# TRNG.net
KiCad netlist of a schematic drawn in EAGLE
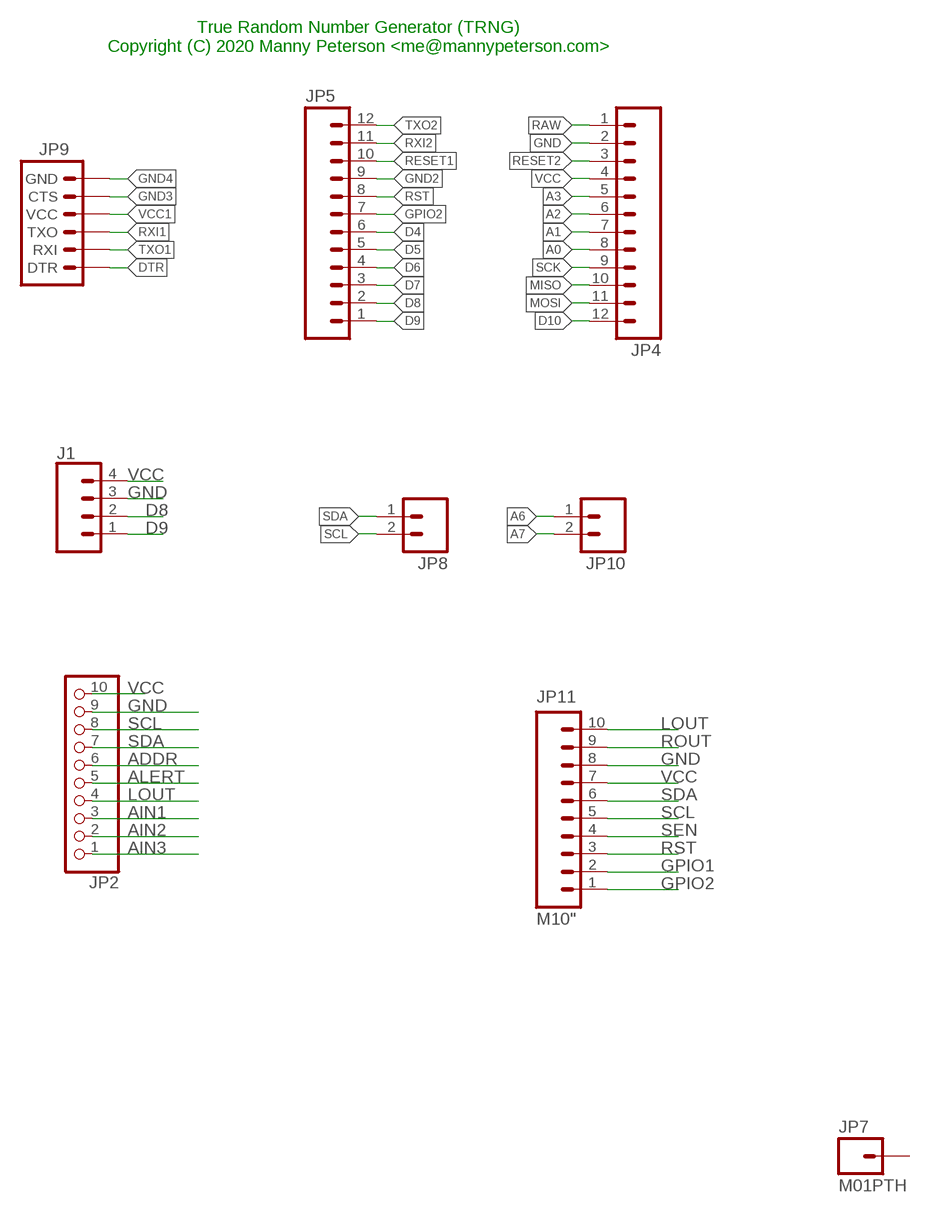
[diagram p0: schematic, sheet 1]

(export (version "E")
  (design (tool "Eeschema 10.0.6"))
  (components
    (comp (ref "J1")
      (value "CONN_04PTH")
      (footprint "eagle-import:1X04")
      (libsource (lib "eagle-import") (part "CONN_04PTH"))
    )
    (comp (ref "JP2")
      (value "HEADER-1X1070MIL")
      (footprint "eagle-import:1X10_ROUND70")
      (libsource (lib "eagle-import") (part "HEADER-1X1070MIL"))
    )
    (comp (ref "JP4")
      (value "M12PTH")
      (footprint "eagle-import:1X12")
      (libsource (lib "eagle-import") (part "M12PTH"))
    )
    (comp (ref "JP5")
      (value "M12PTH")
      (footprint "eagle-import:1X12")
      (libsource (lib "eagle-import") (part "M12PTH"))
    )
    (comp (ref "JP7")
      (value "M01PTH")
      (footprint "eagle-import:1X01")
      (libsource (lib "eagle-import") (part "M01PTH"))
    )
    (comp (ref "JP8")
      (value "M02PTH")
      (footprint "eagle-import:1X02")
      (libsource (lib "eagle-import") (part "M02PTH"))
    )
    (comp (ref "JP9")
      (value "ARDUINO_SERIAL_PROGRAMPTH")
      (footprint "eagle-import:1X06")
      (libsource (lib "eagle-import") (part "ARDUINO_SERIAL_PROGRAMPTH"))
    )
    (comp (ref "JP10")
      (value "M02PTH")
      (footprint "eagle-import:1X02")
      (libsource (lib "eagle-import") (part "M02PTH"))
    )
    (comp (ref "JP11")
      (value "M10\"")
      (footprint "eagle-import:1X10")
      (libsource (lib "eagle-import") (part "M10{dblquote}"))
    )
  )
  (nets
    (net (code "1") (name "/ADDR") (class "Default")
      (node (ref "JP2") (pin "6") (pinfunction "6_6") (pintype "passive"))
    )
    (net (code "2") (name "/AIN1") (class "Default")
      (node (ref "JP2") (pin "3") (pinfunction "3_3") (pintype "passive"))
    )
    (net (code "3") (name "/AIN2") (class "Default")
      (node (ref "JP2") (pin "2") (pinfunction "2_2") (pintype "passive"))
    )
    (net (code "4") (name "/AIN3") (class "Default")
      (node (ref "JP2") (pin "1") (pinfunction "1_1") (pintype "passive"))
    )
    (net (code "5") (name "/ALERT") (class "Default")
      (node (ref "JP2") (pin "5") (pinfunction "5_5") (pintype "passive"))
    )
    (net (code "6") (name "/GPIO1") (class "Default")
      (node (ref "JP11") (pin "2") (pinfunction "2_2") (pintype "passive"))
    )
    (net (code "7") (name "/LOUT") (class "Default")
      (node (ref "JP11") (pin "10") (pinfunction "10_10") (pintype "passive"))
      (node (ref "JP2") (pin "4") (pinfunction "4_4") (pintype "passive"))
    )
    (net (code "8") (name "/ROUT") (class "Default")
      (node (ref "JP11") (pin "9") (pinfunction "9_9") (pintype "passive"))
    )
    (net (code "9") (name "/SEN") (class "Default")
      (node (ref "JP11") (pin "4") (pinfunction "4_4") (pintype "passive"))
    )
    (net (code "10") (name "A0") (class "Default")
      (node (ref "JP4") (pin "8") (pinfunction "8_8") (pintype "passive"))
    )
    (net (code "11") (name "A1") (class "Default")
      (node (ref "JP4") (pin "7") (pinfunction "7_7") (pintype "passive"))
    )
    (net (code "12") (name "A2") (class "Default")
      (node (ref "JP4") (pin "6") (pinfunction "6_6") (pintype "passive"))
    )
    (net (code "13") (name "A3") (class "Default")
      (node (ref "JP4") (pin "5") (pinfunction "5_5") (pintype "passive"))
    )
    (net (code "14") (name "A6") (class "Default")
      (node (ref "JP10") (pin "1") (pinfunction "1_1") (pintype "passive"))
    )
    (net (code "15") (name "A7") (class "Default")
      (node (ref "JP10") (pin "2") (pinfunction "2_2") (pintype "passive"))
    )
    (net (code "16") (name "D4") (class "Default")
      (node (ref "JP5") (pin "6") (pinfunction "6_6") (pintype "passive"))
    )
    (net (code "17") (name "D5") (class "Default")
      (node (ref "JP5") (pin "5") (pinfunction "5_5") (pintype "passive"))
    )
    (net (code "18") (name "D6") (class "Default")
      (node (ref "JP5") (pin "4") (pinfunction "4_4") (pintype "passive"))
    )
    (net (code "19") (name "D7") (class "Default")
      (node (ref "JP5") (pin "3") (pinfunction "3_3") (pintype "passive"))
    )
    (net (code "20") (name "D8") (class "Default")
      (node (ref "J1") (pin "2") (pinfunction "2_2") (pintype "passive"))
      (node (ref "JP5") (pin "2") (pinfunction "2_2") (pintype "passive"))
    )
    (net (code "21") (name "D9") (class "Default")
      (node (ref "J1") (pin "1") (pinfunction "1_1") (pintype "passive"))
      (node (ref "JP5") (pin "1") (pinfunction "1_1") (pintype "passive"))
    )
    (net (code "22") (name "D10") (class "Default")
      (node (ref "JP4") (pin "12") (pinfunction "12_12") (pintype "passive"))
    )
    (net (code "23") (name "DTR") (class "Default")
      (node (ref "JP9") (pin "1") (pinfunction "DTR_1") (pintype "passive"))
    )
    (net (code "24") (name "GND") (class "Default")
      (node (ref "J1") (pin "3") (pinfunction "3_3") (pintype "passive"))
      (node (ref "JP11") (pin "8") (pinfunction "8_8") (pintype "passive"))
      (node (ref "JP2") (pin "9") (pinfunction "9_9") (pintype "passive"))
      (node (ref "JP4") (pin "2") (pinfunction "2_2") (pintype "passive"))
    )
    (net (code "25") (name "GND2") (class "Default")
      (node (ref "JP5") (pin "9") (pinfunction "9_9") (pintype "passive"))
    )
    (net (code "26") (name "GND3") (class "Default")
      (node (ref "JP9") (pin "5") (pinfunction "CTS_5") (pintype "passive"))
    )
    (net (code "27") (name "GND4") (class "Default")
      (node (ref "JP9") (pin "6") (pinfunction "GND_6") (pintype "passive"))
    )
    (net (code "28") (name "GPIO2") (class "Default")
      (node (ref "JP11") (pin "1") (pinfunction "1_1") (pintype "passive"))
      (node (ref "JP5") (pin "7") (pinfunction "7_7") (pintype "passive"))
    )
    (net (code "29") (name "MISO") (class "Default")
      (node (ref "JP4") (pin "10") (pinfunction "10_10") (pintype "passive"))
    )
    (net (code "30") (name "MOSI") (class "Default")
      (node (ref "JP4") (pin "11") (pinfunction "11_11") (pintype "passive"))
    )
    (net (code "31") (name "RAW") (class "Default")
      (node (ref "JP4") (pin "1") (pinfunction "1_1") (pintype "passive"))
    )
    (net (code "32") (name "RESET1") (class "Default")
      (node (ref "JP5") (pin "10") (pinfunction "10_10") (pintype "passive"))
    )
    (net (code "33") (name "RESET2") (class "Default")
      (node (ref "JP4") (pin "3") (pinfunction "3_3") (pintype "passive"))
    )
    (net (code "34") (name "RST") (class "Default")
      (node (ref "JP11") (pin "3") (pinfunction "3_3") (pintype "passive"))
      (node (ref "JP5") (pin "8") (pinfunction "8_8") (pintype "passive"))
    )
    (net (code "35") (name "RXI1") (class "Default")
      (node (ref "JP9") (pin "3") (pinfunction "TXO_3") (pintype "passive"))
    )
    (net (code "36") (name "RXI2") (class "Default")
      (node (ref "JP5") (pin "11") (pinfunction "11_11") (pintype "passive"))
    )
    (net (code "37") (name "SCK") (class "Default")
      (node (ref "JP4") (pin "9") (pinfunction "9_9") (pintype "passive"))
    )
    (net (code "38") (name "SCL") (class "Default")
      (node (ref "JP11") (pin "5") (pinfunction "5_5") (pintype "passive"))
      (node (ref "JP2") (pin "8") (pinfunction "8_8") (pintype "passive"))
      (node (ref "JP8") (pin "2") (pinfunction "2_2") (pintype "passive"))
    )
    (net (code "39") (name "SDA") (class "Default")
      (node (ref "JP11") (pin "6") (pinfunction "6_6") (pintype "passive"))
      (node (ref "JP2") (pin "7") (pinfunction "7_7") (pintype "passive"))
      (node (ref "JP8") (pin "1") (pinfunction "1_1") (pintype "passive"))
    )
    (net (code "40") (name "TXO1") (class "Default")
      (node (ref "JP9") (pin "2") (pinfunction "RXI_2") (pintype "passive"))
    )
    (net (code "41") (name "TXO2") (class "Default")
      (node (ref "JP5") (pin "12") (pinfunction "12_12") (pintype "passive"))
    )
    (net (code "42") (name "VCC") (class "Default")
      (node (ref "J1") (pin "4") (pinfunction "4_4") (pintype "passive"))
      (node (ref "JP11") (pin "7") (pinfunction "7_7") (pintype "passive"))
      (node (ref "JP2") (pin "10") (pinfunction "10_10") (pintype "passive"))
      (node (ref "JP4") (pin "4") (pinfunction "4_4") (pintype "passive"))
    )
    (net (code "43") (name "VCC1") (class "Default")
      (node (ref "JP9") (pin "4") (pinfunction "VCC_4") (pintype "passive"))
    )
    (net (code "44") (name "unconnected-(JP7-Pad1)") (class "Default")
      (node (ref "JP7") (pin "1") (pinfunction "1_1") (pintype "passive"))
    )
  )
)
